# MOTOR_DRV.net
KiCad netlist of a schematic drawn in Altium Designer
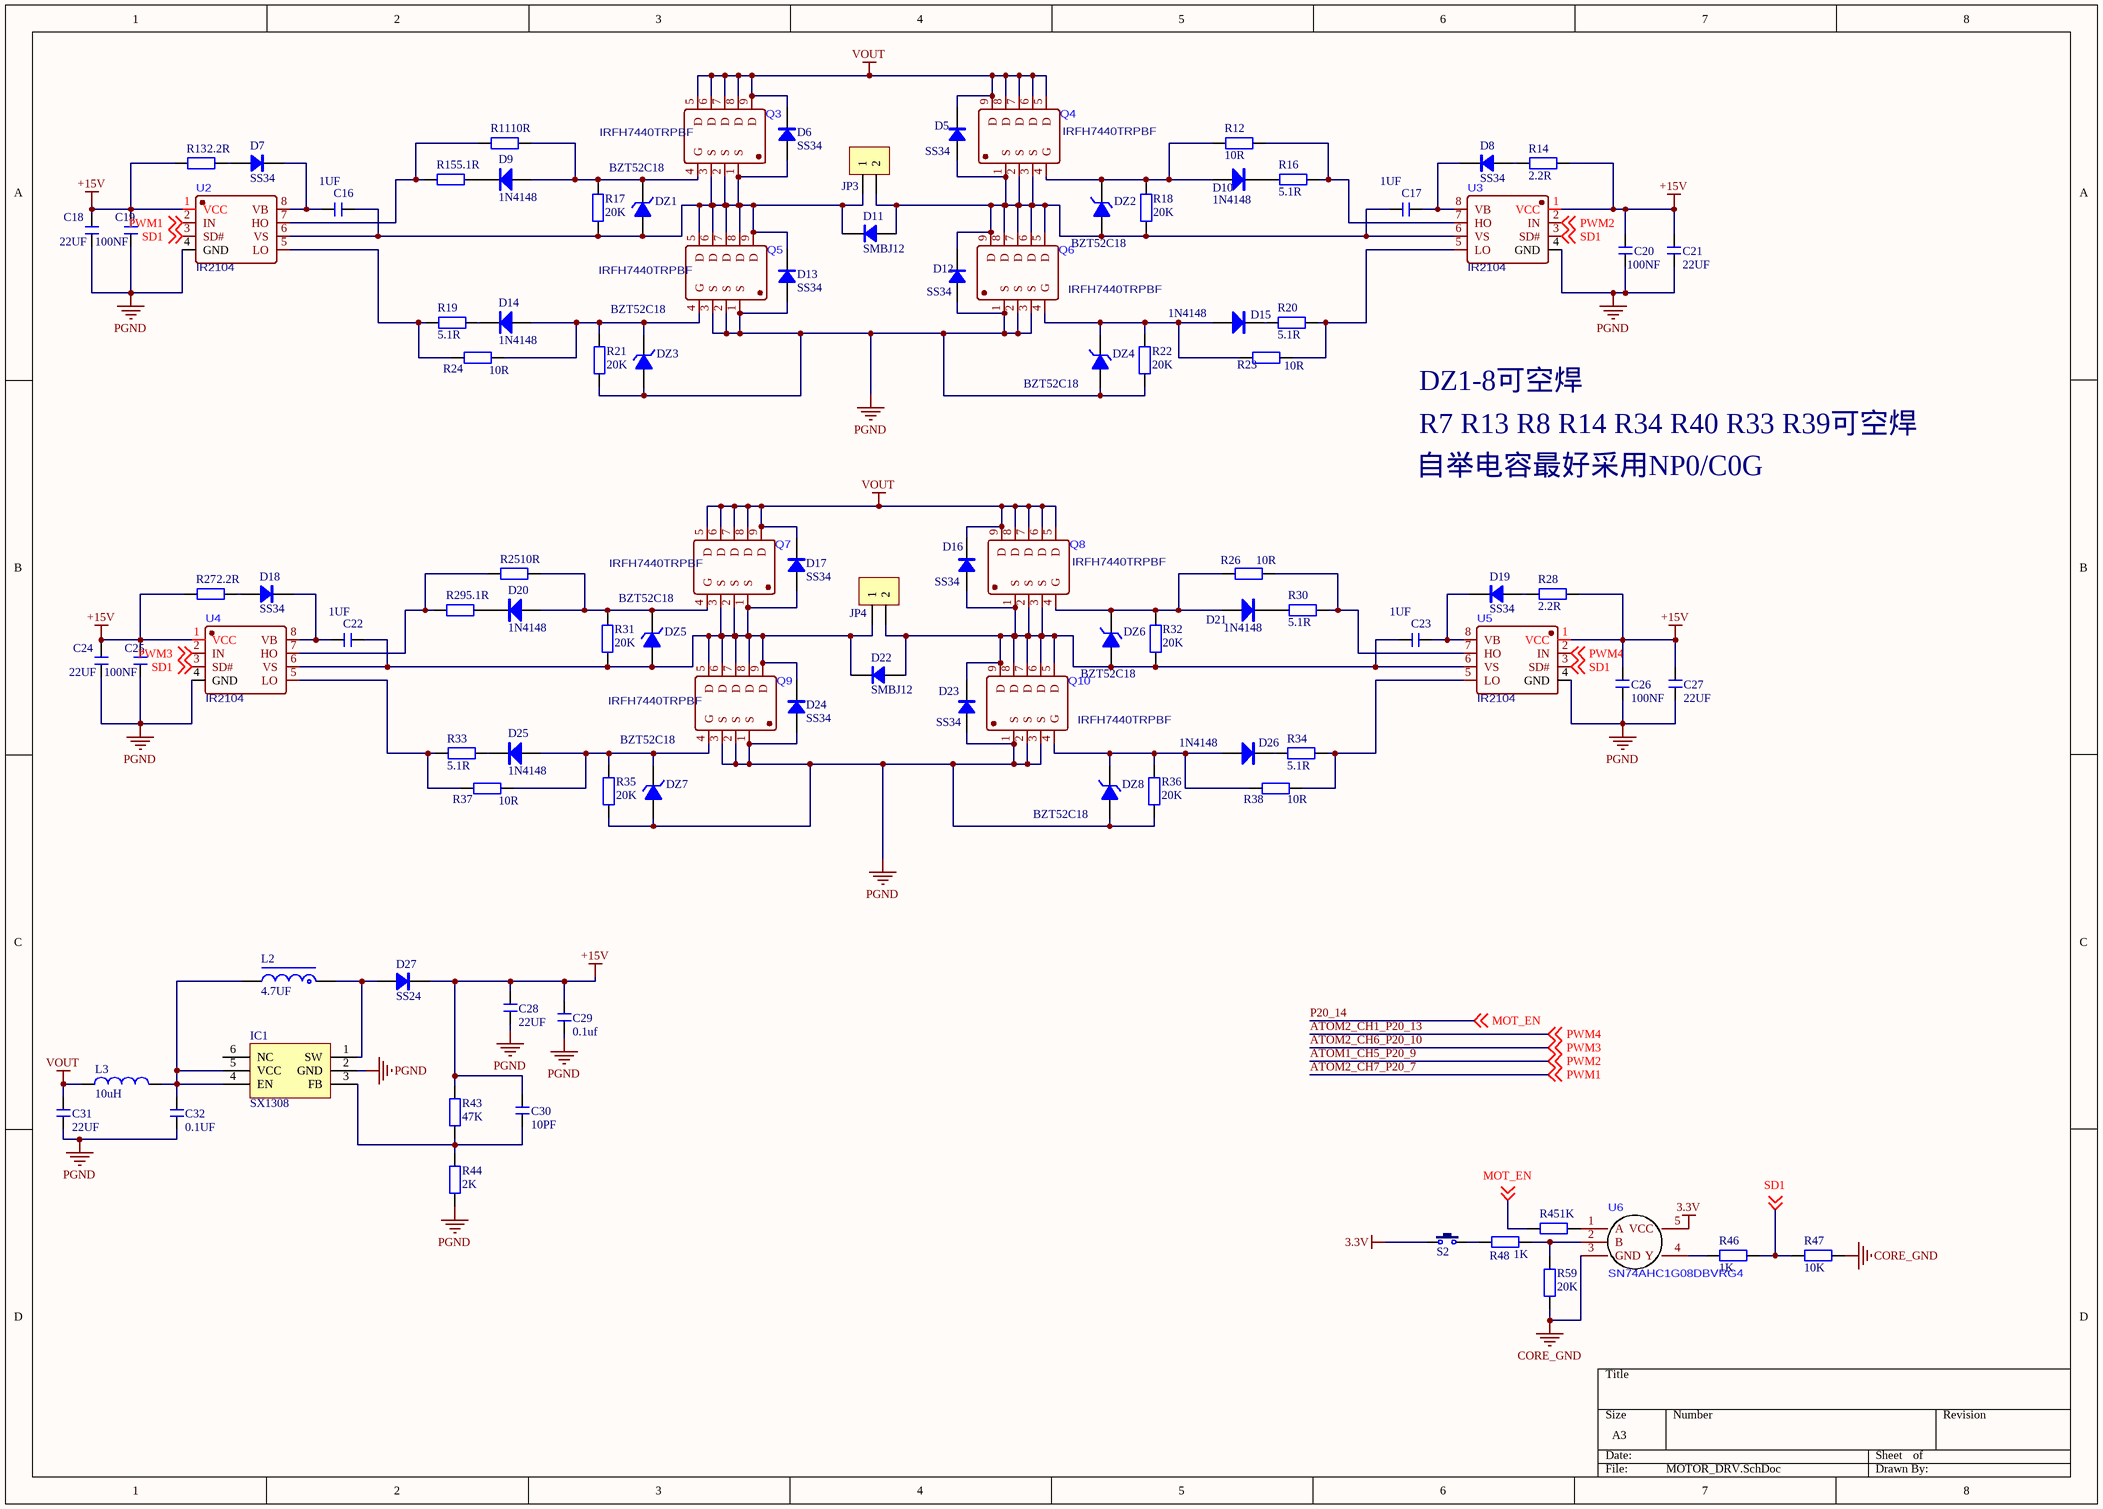
[diagram p0: MOTOR_DRV.SchDoc]

(export (version "E")
  (design (tool "Eeschema 10.0.6"))
  (components
    (comp (ref "C16")
      (value "1UF")
      (footprint "C 1206_L")
      (description "无极性贴片电容")
      (fields (field (name "版权归属") "源创客"))
      (libsource (lib "3.1   - 电阻-电容-电感") (part "C"))
    )
    (comp (ref "C17")
      (value "1UF")
      (footprint "C 1206_L")
      (description "无极性贴片电容")
      (fields (field (name "版权归属") "源创客"))
      (libsource (lib "3.1   - 电阻-电容-电感") (part "C"))
    )
    (comp (ref "C18")
      (value "22UF")
      (footprint "C 0805_L")
      (description "无极性贴片电容")
      (fields (field (name "版权归属") "源创客"))
      (libsource (lib "3.1   - 电阻-电容-电感") (part "C"))
    )
    (comp (ref "C19")
      (value "100NF")
      (footprint "C 0805_L")
      (description "无极性贴片电容")
      (fields (field (name "版权归属") "源创客"))
      (libsource (lib "3.1   - 电阻-电容-电感") (part "C"))
    )
    (comp (ref "C20")
      (value "100NF")
      (footprint "C 0805_L")
      (description "无极性贴片电容")
      (fields (field (name "版权归属") "源创客"))
      (libsource (lib "3.1   - 电阻-电容-电感") (part "C"))
    )
    (comp (ref "C21")
      (value "22UF")
      (footprint "C 0805_L")
      (description "无极性贴片电容")
      (fields (field (name "版权归属") "源创客"))
      (libsource (lib "3.1   - 电阻-电容-电感") (part "C"))
    )
    (comp (ref "C22")
      (value "1UF")
      (footprint "C 1206_L")
      (description "无极性贴片电容")
      (fields (field (name "版权归属") "源创客"))
      (libsource (lib "3.1   - 电阻-电容-电感") (part "C"))
    )
    (comp (ref "C23")
      (value "1UF")
      (footprint "C 1206_L")
      (description "无极性贴片电容")
      (fields (field (name "版权归属") "源创客"))
      (libsource (lib "3.1   - 电阻-电容-电感") (part "C"))
    )
    (comp (ref "C24")
      (value "22UF")
      (footprint "C 0805_L")
      (description "无极性贴片电容")
      (fields (field (name "版权归属") "源创客"))
      (libsource (lib "3.1   - 电阻-电容-电感") (part "C"))
    )
    (comp (ref "C25")
      (value "100NF")
      (footprint "C 0805_L")
      (description "无极性贴片电容")
      (fields (field (name "版权归属") "源创客"))
      (libsource (lib "3.1   - 电阻-电容-电感") (part "C"))
    )
    (comp (ref "C26")
      (value "100NF")
      (footprint "C 0805_L")
      (description "无极性贴片电容")
      (fields (field (name "版权归属") "源创客"))
      (libsource (lib "3.1   - 电阻-电容-电感") (part "C"))
    )
    (comp (ref "C27")
      (value "22UF")
      (footprint "C 0805_L")
      (description "无极性贴片电容")
      (fields (field (name "版权归属") "源创客"))
      (libsource (lib "3.1   - 电阻-电容-电感") (part "C"))
    )
    (comp (ref "C28")
      (value "22UF")
      (footprint "C 0805_L")
      (description "无极性贴片电容")
      (fields (field (name "版权归属") "源创客"))
      (libsource (lib "3.1   - 电阻-电容-电感") (part "C"))
    )
    (comp (ref "C29")
      (value "0.1uf")
      (footprint "C 0805_L")
      (description "无极性贴片电容")
      (fields (field (name "版权归属") "源创客"))
      (libsource (lib "3.1   - 电阻-电容-电感") (part "C"))
    )
    (comp (ref "C30")
      (value "10PF")
      (footprint "C 0805_L")
      (description "无极性贴片电容")
      (fields (field (name "版权归属") "源创客"))
      (libsource (lib "3.1   - 电阻-电容-电感") (part "C"))
    )
    (comp (ref "C31")
      (value "22UF")
      (footprint "C 0805_L")
      (description "无极性贴片电容")
      (fields (field (name "版权归属") "源创客"))
      (libsource (lib "3.1   - 电阻-电容-电感") (part "C"))
    )
    (comp (ref "C32")
      (value "0.1UF")
      (footprint "C 0805_L")
      (description "无极性贴片电容")
      (fields (field (name "版权归属") "源创客"))
      (libsource (lib "3.1   - 电阻-电容-电感") (part "C"))
    )
    (comp (ref "D5")
      (value "SS34")
      (footprint "SMA")
      (description "肖特基二极管")
      (fields (field (name "版权归属") "源创客"))
      (libsource (lib "8.1   - 二极管-整流桥") (part "SS34"))
    )
    (comp (ref "D6")
      (value "SS34")
      (footprint "SMA")
      (description "肖特基二极管")
      (fields (field (name "版权归属") "源创客"))
      (libsource (lib "8.1   - 二极管-整流桥") (part "SS34"))
    )
    (comp (ref "D7")
      (value "SS34")
      (footprint "SMA")
      (description "肖特基二极管")
      (fields (field (name "版权归属") "源创客"))
      (libsource (lib "8.1   - 二极管-整流桥") (part "SS34"))
    )
    (comp (ref "D8")
      (value "SS34")
      (footprint "SMA")
      (description "肖特基二极管")
      (fields (field (name "版权归属") "源创客"))
      (libsource (lib "8.1   - 二极管-整流桥") (part "SS34"))
    )
    (comp (ref "D9")
      (value "1N4148")
      (footprint "SOD-123")
      (description "高速开关二极管")
      (fields (field (name "版权归属") "源创客"))
      (libsource (lib "8.1   - 二极管-整流桥") (part "1N4148"))
    )
    (comp (ref "D10")
      (value "1N4148")
      (footprint "SOD-123")
      (description "高速开关二极管")
      (fields (field (name "版权归属") "源创客"))
      (libsource (lib "8.1   - 二极管-整流桥") (part "1N4148"))
    )
    (comp (ref "D11")
      (value "SMBJ12")
      (footprint "SMA")
      (description "肖特基二极管")
      (fields (field (name "版权归属") "源创客"))
      (libsource (lib "8.1   - 二极管-整流桥") (part "SS34"))
    )
    (comp (ref "D12")
      (value "SS34")
      (footprint "SMA")
      (description "肖特基二极管")
      (fields (field (name "版权归属") "源创客"))
      (libsource (lib "8.1   - 二极管-整流桥") (part "SS34"))
    )
    (comp (ref "D13")
      (value "SS34")
      (footprint "SMA")
      (description "肖特基二极管")
      (fields (field (name "版权归属") "源创客"))
      (libsource (lib "8.1   - 二极管-整流桥") (part "SS34"))
    )
    (comp (ref "D14")
      (value "1N4148")
      (footprint "SOD-123")
      (description "高速开关二极管")
      (fields (field (name "版权归属") "源创客"))
      (libsource (lib "8.1   - 二极管-整流桥") (part "1N4148"))
    )
    (comp (ref "D15")
      (value "1N4148")
      (footprint "SOD-123")
      (description "高速开关二极管")
      (fields (field (name "版权归属") "源创客"))
      (libsource (lib "8.1   - 二极管-整流桥") (part "1N4148"))
    )
    (comp (ref "D16")
      (value "SS34")
      (footprint "SMA")
      (description "肖特基二极管")
      (fields (field (name "版权归属") "源创客"))
      (libsource (lib "8.1   - 二极管-整流桥") (part "SS34"))
    )
    (comp (ref "D17")
      (value "SS34")
      (footprint "SMA")
      (description "肖特基二极管")
      (fields (field (name "版权归属") "源创客"))
      (libsource (lib "8.1   - 二极管-整流桥") (part "SS34"))
    )
    (comp (ref "D18")
      (value "SS34")
      (footprint "SMA")
      (description "肖特基二极管")
      (fields (field (name "版权归属") "源创客"))
      (libsource (lib "8.1   - 二极管-整流桥") (part "SS34"))
    )
    (comp (ref "D19")
      (value "SS34")
      (footprint "SMA")
      (description "肖特基二极管")
      (fields (field (name "版权归属") "源创客"))
      (libsource (lib "8.1   - 二极管-整流桥") (part "SS34"))
    )
    (comp (ref "D20")
      (value "1N4148")
      (footprint "SOD-123")
      (description "高速开关二极管")
      (fields (field (name "版权归属") "源创客"))
      (libsource (lib "8.1   - 二极管-整流桥") (part "1N4148"))
    )
    (comp (ref "D21")
      (value "1N4148")
      (footprint "SOD-123")
      (description "高速开关二极管")
      (fields (field (name "版权归属") "源创客"))
      (libsource (lib "8.1   - 二极管-整流桥") (part "1N4148"))
    )
    (comp (ref "D22")
      (value "SMBJ12")
      (footprint "SMA")
      (description "肖特基二极管")
      (fields (field (name "版权归属") "源创客"))
      (libsource (lib "8.1   - 二极管-整流桥") (part "SS34"))
    )
    (comp (ref "D23")
      (value "SS34")
      (footprint "SMA")
      (description "肖特基二极管")
      (fields (field (name "版权归属") "源创客"))
      (libsource (lib "8.1   - 二极管-整流桥") (part "SS34"))
    )
    (comp (ref "D24")
      (value "SS34")
      (footprint "SMA")
      (description "肖特基二极管")
      (fields (field (name "版权归属") "源创客"))
      (libsource (lib "8.1   - 二极管-整流桥") (part "SS34"))
    )
    (comp (ref "D25")
      (value "1N4148")
      (footprint "SOD-123")
      (description "高速开关二极管")
      (fields (field (name "版权归属") "源创客"))
      (libsource (lib "8.1   - 二极管-整流桥") (part "1N4148"))
    )
    (comp (ref "D26")
      (value "1N4148")
      (footprint "SOD-123")
      (description "高速开关二极管")
      (fields (field (name "版权归属") "源创客"))
      (libsource (lib "8.1   - 二极管-整流桥") (part "1N4148"))
    )
    (comp (ref "D27")
      (value "SS24")
      (footprint "SMA")
      (description "肖特基二极管")
      (fields (field (name "版权归属") "源创客"))
      (libsource (lib "8.1   - 二极管-整流桥") (part "SS24"))
    )
    (comp (ref "DZ1")
      (value "BZT52C18")
      (footprint "SOD-123")
      (description "18V稳压管")
      (fields (field (name "版权归属") "源创客"))
      (libsource (lib "8.1   - 二极管-整流桥") (part "1N4102"))
    )
    (comp (ref "DZ2")
      (value "BZT52C18")
      (footprint "SOD-123")
      (description "18V稳压管")
      (fields (field (name "版权归属") "源创客"))
      (libsource (lib "8.1   - 二极管-整流桥") (part "1N4102"))
    )
    (comp (ref "DZ3")
      (value "BZT52C18")
      (footprint "SOD-123")
      (description "18V稳压管")
      (fields (field (name "版权归属") "源创客"))
      (libsource (lib "8.1   - 二极管-整流桥") (part "1N4102"))
    )
    (comp (ref "DZ4")
      (value "BZT52C18")
      (footprint "SOD-123")
      (description "18V稳压管")
      (fields (field (name "版权归属") "源创客"))
      (libsource (lib "8.1   - 二极管-整流桥") (part "1N4102"))
    )
    (comp (ref "DZ5")
      (value "BZT52C18")
      (footprint "SOD-123")
      (description "18V稳压管")
      (fields (field (name "版权归属") "源创客"))
      (libsource (lib "8.1   - 二极管-整流桥") (part "1N4102"))
    )
    (comp (ref "DZ6")
      (value "BZT52C18")
      (footprint "SOD-123")
      (description "18V稳压管")
      (fields (field (name "版权归属") "源创客"))
      (libsource (lib "8.1   - 二极管-整流桥") (part "1N4102"))
    )
    (comp (ref "DZ7")
      (value "BZT52C18")
      (footprint "SOD-123")
      (description "18V稳压管")
      (fields (field (name "版权归属") "源创客"))
      (libsource (lib "8.1   - 二极管-整流桥") (part "1N4102"))
    )
    (comp (ref "DZ8")
      (value "BZT52C18")
      (footprint "SOD-123")
      (description "18V稳压管")
      (fields (field (name "版权归属") "源创客"))
      (libsource (lib "8.1   - 二极管-整流桥") (part "1N4102"))
    )
    (comp (ref "IC1")
      (value "SX1308")
      (footprint "SOT23-6N")
      (description "可调升压芯片")
      (fields (field (name "版权归属") "源创客"))
      (libsource (lib "1.3   - 电源类芯片") (part "SX1308"))
    )
    (comp (ref "JP3")
      (value "HDR-1X2")
      (footprint "KF2EDGK5.08-LI-2P")
      (description "2P接插件")
      (fields (field (name "版权归属") "源创客"))
      (libsource (lib "4.11 - 接插件-脚距5.08") (part "Header 2"))
    )
    (comp (ref "JP4")
      (value "HDR-1X2")
      (footprint "KF2EDGK5.08-LI-2P")
      (description "2P接插件")
      (fields (field (name "版权归属") "源创客"))
      (libsource (lib "4.11 - 接插件-脚距5.08") (part "Header 2"))
    )
    (comp (ref "L2")
      (value "4.7UF")
      (footprint "L-SMD-0630")
      (description "功率屏蔽电感")
      (fields (field (name "版权归属") "源创客"))
      (libsource (lib "3.1   - 电阻-电容-电感") (part "L-CDRH"))
    )
    (comp (ref "L3")
      (value "10uH")
      (footprint "L 0805_L")
      (description "小功率贴片电感")
      (fields (field (name "版权归属") "源创客"))
      (libsource (lib "3.1   - 电阻-电容-电感") (part "L"))
    )
    (comp (ref "Q3")
      (value "IRFH7440TRPBF")
      (footprint "PQFN-8P_L5.8-W4.9-P1.27-LS6.0-BL")
      (libsource (lib "IRFH7440TRPBF") (part "IRFH7440TRPBF"))
    )
    (comp (ref "Q4")
      (value "IRFH7440TRPBF")
      (footprint "PQFN-8P_L5.8-W4.9-P1.27-LS6.0-BL")
      (libsource (lib "IRFH7440TRPBF") (part "IRFH7440TRPBF"))
    )
    (comp (ref "Q5")
      (value "IRFH7440TRPBF")
      (footprint "PQFN-8P_L5.8-W4.9-P1.27-LS6.0-BL")
      (libsource (lib "IRFH7440TRPBF") (part "IRFH7440TRPBF"))
    )
    (comp (ref "Q6")
      (value "IRFH7440TRPBF")
      (footprint "PQFN-8P_L5.8-W4.9-P1.27-LS6.0-BL")
      (libsource (lib "IRFH7440TRPBF") (part "IRFH7440TRPBF"))
    )
    (comp (ref "Q7")
      (value "IRFH7440TRPBF")
      (footprint "PQFN-8P_L5.8-W4.9-P1.27-LS6.0-BL")
      (libsource (lib "IRFH7440TRPBF") (part "IRFH7440TRPBF"))
    )
    (comp (ref "Q8")
      (value "IRFH7440TRPBF")
      (footprint "PQFN-8P_L5.8-W4.9-P1.27-LS6.0-BL")
      (libsource (lib "IRFH7440TRPBF") (part "IRFH7440TRPBF"))
    )
    (comp (ref "Q9")
      (value "IRFH7440TRPBF")
      (footprint "PQFN-8P_L5.8-W4.9-P1.27-LS6.0-BL")
      (libsource (lib "IRFH7440TRPBF") (part "IRFH7440TRPBF"))
    )
    (comp (ref "Q10")
      (value "IRFH7440TRPBF")
      (footprint "PQFN-8P_L5.8-W4.9-P1.27-LS6.0-BL")
      (libsource (lib "IRFH7440TRPBF") (part "IRFH7440TRPBF"))
    )
    (comp (ref "R11")
      (value "10R")
      (footprint "R 0805_L")
      (description "贴片电阻")
      (fields (field (name "版权归属") "源创客"))
      (libsource (lib "3.1   - 电阻-电容-电感") (part "R"))
    )
    (comp (ref "R12")
      (value "10R")
      (footprint "R 0805_L")
      (description "贴片电阻")
      (fields (field (name "版权归属") "源创客"))
      (libsource (lib "3.1   - 电阻-电容-电感") (part "R"))
    )
    (comp (ref "R13")
      (value "2.2R")
      (footprint "R 0805_L")
      (description "贴片电阻")
      (fields (field (name "版权归属") "源创客"))
      (libsource (lib "3.1   - 电阻-电容-电感") (part "R"))
    )
    (comp (ref "R14")
      (value "2.2R")
      (footprint "R 0805_L")
      (description "贴片电阻")
      (fields (field (name "版权归属") "源创客"))
      (libsource (lib "3.1   - 电阻-电容-电感") (part "R"))
    )
    (comp (ref "R15")
      (value "5.1R")
      (footprint "R 0805_L")
      (description "贴片电阻")
      (fields (field (name "版权归属") "源创客"))
      (libsource (lib "3.1   - 电阻-电容-电感") (part "R"))
    )
    (comp (ref "R16")
      (value "5.1R")
      (footprint "R 0805_L")
      (description "贴片电阻")
      (fields (field (name "版权归属") "源创客"))
      (libsource (lib "3.1   - 电阻-电容-电感") (part "R"))
    )
    (comp (ref "R17")
      (value "20K")
      (footprint "R 0805_L")
      (description "贴片电阻")
      (fields (field (name "版权归属") "源创客"))
      (libsource (lib "3.1   - 电阻-电容-电感") (part "R"))
    )
    (comp (ref "R18")
      (value "20K")
      (footprint "R 0805_L")
      (description "贴片电阻")
      (fields (field (name "版权归属") "源创客"))
      (libsource (lib "3.1   - 电阻-电容-电感") (part "R"))
    )
    (comp (ref "R19")
      (value "5.1R")
      (footprint "R 0805_L")
      (description "贴片电阻")
      (fields (field (name "版权归属") "源创客"))
      (libsource (lib "3.1   - 电阻-电容-电感") (part "R"))
    )
    (comp (ref "R20")
      (value "5.1R")
      (footprint "R 0805_L")
      (description "贴片电阻")
      (fields (field (name "版权归属") "源创客"))
      (libsource (lib "3.1   - 电阻-电容-电感") (part "R"))
    )
    (comp (ref "R21")
      (value "20K")
      (footprint "R 0805_L")
      (description "贴片电阻")
      (fields (field (name "版权归属") "源创客"))
      (libsource (lib "3.1   - 电阻-电容-电感") (part "R"))
    )
    (comp (ref "R22")
      (value "20K")
      (footprint "R 0805_L")
      (description "贴片电阻")
      (fields (field (name "版权归属") "源创客"))
      (libsource (lib "3.1   - 电阻-电容-电感") (part "R"))
    )
    (comp (ref "R23")
      (value "10R")
      (footprint "R 0805_L")
      (description "贴片电阻")
      (fields (field (name "版权归属") "源创客"))
      (libsource (lib "3.1   - 电阻-电容-电感") (part "R"))
    )
    (comp (ref "R24")
      (value "10R")
      (footprint "R 0805_L")
      (description "贴片电阻")
      (fields (field (name "版权归属") "源创客"))
      (libsource (lib "3.1   - 电阻-电容-电感") (part "R"))
    )
    (comp (ref "R25")
      (value "10R")
      (footprint "R 0805_L")
      (description "贴片电阻")
      (fields (field (name "版权归属") "源创客"))
      (libsource (lib "3.1   - 电阻-电容-电感") (part "R"))
    )
    (comp (ref "R26")
      (value "10R")
      (footprint "R 0805_L")
      (description "贴片电阻")
      (fields (field (name "版权归属") "源创客"))
      (libsource (lib "3.1   - 电阻-电容-电感") (part "R"))
    )
    (comp (ref "R27")
      (value "2.2R")
      (footprint "R 0805_L")
      (description "贴片电阻")
      (fields (field (name "版权归属") "源创客"))
      (libsource (lib "3.1   - 电阻-电容-电感") (part "R"))
    )
    (comp (ref "R28")
      (value "2.2R")
      (footprint "R 0805_L")
      (description "贴片电阻")
      (fields (field (name "版权归属") "源创客"))
      (libsource (lib "3.1   - 电阻-电容-电感") (part "R"))
    )
    (comp (ref "R29")
      (value "5.1R")
      (footprint "R 0805_L")
      (description "贴片电阻")
      (fields (field (name "版权归属") "源创客"))
      (libsource (lib "3.1   - 电阻-电容-电感") (part "R"))
    )
    (comp (ref "R30")
      (value "5.1R")
      (footprint "R 0805_L")
      (description "贴片电阻")
      (fields (field (name "版权归属") "源创客"))
      (libsource (lib "3.1   - 电阻-电容-电感") (part "R"))
    )
    (comp (ref "R31")
      (value "20K")
      (footprint "R 0805_L")
      (description "贴片电阻")
      (fields (field (name "版权归属") "源创客"))
      (libsource (lib "3.1   - 电阻-电容-电感") (part "R"))
    )
    (comp (ref "R32")
      (value "20K")
      (footprint "R 0805_L")
      (description "贴片电阻")
      (fields (field (name "版权归属") "源创客"))
      (libsource (lib "3.1   - 电阻-电容-电感") (part "R"))
    )
    (comp (ref "R33")
      (value "5.1R")
      (footprint "R 0805_L")
      (description "贴片电阻")
      (fields (field (name "版权归属") "源创客"))
      (libsource (lib "3.1   - 电阻-电容-电感") (part "R"))
    )
    (comp (ref "R34")
      (value "5.1R")
      (footprint "R 0805_L")
      (description "贴片电阻")
      (fields (field (name "版权归属") "源创客"))
      (libsource (lib "3.1   - 电阻-电容-电感") (part "R"))
    )
    (comp (ref "R35")
      (value "20K")
      (footprint "R 0805_L")
      (description "贴片电阻")
      (fields (field (name "版权归属") "源创客"))
      (libsource (lib "3.1   - 电阻-电容-电感") (part "R"))
    )
    (comp (ref "R36")
      (value "20K")
      (footprint "R 0805_L")
      (description "贴片电阻")
      (fields (field (name "版权归属") "源创客"))
      (libsource (lib "3.1   - 电阻-电容-电感") (part "R"))
    )
    (comp (ref "R37")
      (value "10R")
      (footprint "R 0805_L")
      (description "贴片电阻")
      (fields (field (name "版权归属") "源创客"))
      (libsource (lib "3.1   - 电阻-电容-电感") (part "R"))
    )
    (comp (ref "R38")
      (value "10R")
      (footprint "R 0805_L")
      (description "贴片电阻")
      (fields (field (name "版权归属") "源创客"))
      (libsource (lib "3.1   - 电阻-电容-电感") (part "R"))
    )
    (comp (ref "R43")
      (value "47K")
      (footprint "R 0805_L")
      (description "贴片电阻")
      (fields (field (name "版权归属") "源创客"))
      (libsource (lib "3.1   - 电阻-电容-电感") (part "R"))
    )
    (comp (ref "R44")
      (value "2K")
      (footprint "R 0805_L")
      (description "贴片电阻")
      (fields (field (name "版权归属") "源创客"))
      (libsource (lib "3.1   - 电阻-电容-电感") (part "R"))
    )
    (comp (ref "R45")
      (value "1K")
      (footprint "R 0805_L")
      (description "贴片电阻")
      (fields (field (name "版权归属") "源创客"))
      (libsource (lib "3.1   - 电阻-电容-电感") (part "R"))
    )
    (comp (ref "R46")
      (value "1K")
      (footprint "R 0805_L")
      (description "贴片电阻")
      (fields (field (name "版权归属") "源创客"))
      (libsource (lib "3.1   - 电阻-电容-电感") (part "R"))
    )
    (comp (ref "R47")
      (value "10K")
      (footprint "R 0805_L")
      (description "贴片电阻")
      (fields (field (name "版权归属") "源创客"))
      (libsource (lib "3.1   - 电阻-电容-电感") (part "R"))
    )
    (comp (ref "R48")
      (value "1K")
      (footprint "R 0805_L")
      (description "贴片电阻")
      (fields (field (name "版权归属") "源创客"))
      (libsource (lib "3.1   - 电阻-电容-电感") (part "R"))
    )
    (comp (ref "R59")
      (value "20K")
      (footprint "R 0805_L")
      (description "贴片电阻")
      (fields (field (name "版权归属") "源创客"))
      (libsource (lib "3.1   - 电阻-电容-电感") (part "R"))
    )
    (comp (ref "S2")
      (value "6x6x5")
      (footprint "KEY-TH_CN-KCD11")
      (description "2脚直插6x6轻触开关")
      (fields (field (name "版权归属") "源创客"))
      (libsource (lib "5.1   - 按键-开关") (part "TSW DIP-2Pin-6x6"))
    )
    (comp (ref "U2") (value "IR2104") (footprint "SOP8_M") (libsource (lib "EG2104") (part "EG2104")))
    (comp (ref "U3") (value "IR2104") (footprint "SOP8_M") (libsource (lib "EG2104") (part "EG2104")))
    (comp (ref "U4") (value "IR2104") (footprint "SOP8_M") (libsource (lib "EG2104") (part "EG2104")))
    (comp (ref "U5") (value "IR2104") (footprint "SOP8_M") (libsource (lib "EG2104") (part "EG2104")))
    (comp (ref "U6")
      (value "SN74AHC1G08DBVRG4")
      (footprint "SOT23-5L")
      (libsource (lib "SN74AHC1G08DBVRG4") (part "SN74AHC1G08DBVRG4"))
    )
  )
  (nets
    (net (code "1") (name "+15V") (class "Default")
      (node (ref "C18") (pin "2") (pinfunction "2_2") (pintype "passive"))
      (node (ref "C19") (pin "2") (pinfunction "2_2") (pintype "passive"))
      (node (ref "C20") (pin "2") (pinfunction "2_2") (pintype "passive"))
      (node (ref "C21") (pin "2") (pinfunction "2_2") (pintype "passive"))
      (node (ref "C24") (pin "2") (pinfunction "2_2") (pintype "passive"))
      (node (ref "C25") (pin "2") (pinfunction "2_2") (pintype "passive"))
      (node (ref "C26") (pin "2") (pinfunction "2_2") (pintype "passive"))
      (node (ref "C27") (pin "2") (pinfunction "2_2") (pintype "passive"))
      (node (ref "C28") (pin "1") (pinfunction "1_1") (pintype "passive"))
      (node (ref "C29") (pin "1") (pinfunction "1_1") (pintype "passive"))
      (node (ref "C30") (pin "1") (pinfunction "1_1") (pintype "passive"))
      (node (ref "D27") (pin "2") (pinfunction "K_2") (pintype "passive"))
      (node (ref "R13") (pin "1") (pinfunction "1_1") (pintype "passive"))
      (node (ref "R14") (pin "1") (pinfunction "1_1") (pintype "passive"))
      (node (ref "R27") (pin "1") (pinfunction "1_1") (pintype "passive"))
      (node (ref "R28") (pin "1") (pinfunction "1_1") (pintype "passive"))
      (node (ref "R43") (pin "1") (pinfunction "1_1") (pintype "passive"))
      (node (ref "U2") (pin "1") (pinfunction "VCC_1") (pintype "passive"))
      (node (ref "U3") (pin "1") (pinfunction "VCC_1") (pintype "passive"))
      (node (ref "U4") (pin "1") (pinfunction "VCC_1") (pintype "passive"))
      (node (ref "U5") (pin "1") (pinfunction "VCC_1") (pintype "passive"))
    )
    (net (code "2") (name "3.3V") (class "Default")
      (node (ref "S2") (pin "1") (pinfunction "1_1") (pintype "passive"))
      (node (ref "U6") (pin "5") (pinfunction "VCC_5") (pintype "passive"))
    )
    (net (code "3") (name "CORE_GND") (class "Default")
      (node (ref "R47") (pin "2") (pinfunction "2_2") (pintype "passive"))
      (node (ref "R59") (pin "2") (pinfunction "2_2") (pintype "passive"))
      (node (ref "U6") (pin "3") (pinfunction "GND_3") (pintype "passive"))
    )
    (net (code "4") (name "MOT_EN") (class "Default")
      (node (ref "R45") (pin "2") (pinfunction "2_2") (pintype "passive"))
    )
    (net (code "5") (name "Net-(D7-A)") (class "Default")
      (node (ref "D7") (pin "1") (pinfunction "A_1") (pintype "passive"))
      (node (ref "R13") (pin "2") (pinfunction "2_2") (pintype "passive"))
    )
    (net (code "6") (name "Net-(D7-K)") (class "Default")
      (node (ref "C16") (pin "2") (pinfunction "2_2") (pintype "passive"))
      (node (ref "D7") (pin "2") (pinfunction "K_2") (pintype "passive"))
      (node (ref "U2") (pin "8") (pinfunction "VB_8") (pintype "passive"))
    )
    (net (code "7") (name "Net-(D8-A)") (class "Default")
      (node (ref "D8") (pin "1") (pinfunction "A_1") (pintype "passive"))
      (node (ref "R14") (pin "2") (pinfunction "2_2") (pintype "passive"))
    )
    (net (code "8") (name "Net-(D8-K)") (class "Default")
      (node (ref "C17") (pin "2") (pinfunction "2_2") (pintype "passive"))
      (node (ref "D8") (pin "2") (pinfunction "K_2") (pintype "passive"))
      (node (ref "U3") (pin "8") (pinfunction "VB_8") (pintype "passive"))
    )
    (net (code "9") (name "Net-(D9-A)") (class "Default")
      (node (ref "D9") (pin "1") (pinfunction "A_1") (pintype "passive"))
      (node (ref "DZ1") (pin "2") (pinfunction "K_2") (pintype "passive"))
      (node (ref "Q3") (pin "4") (pinfunction "G_4") (pintype "passive"))
      (node (ref "R11") (pin "2") (pinfunction "2_2") (pintype "passive"))
      (node (ref "R17") (pin "2") (pinfunction "2_2") (pintype "passive"))
    )
    (net (code "10") (name "Net-(D9-K)") (class "Default")
      (node (ref "D9") (pin "2") (pinfunction "K_2") (pintype "passive"))
      (node (ref "R15") (pin "2") (pinfunction "2_2") (pintype "passive"))
    )
    (net (code "11") (name "Net-(D10-A)") (class "Default")
      (node (ref "D10") (pin "1") (pinfunction "A_1") (pintype "passive"))
      (node (ref "DZ2") (pin "2") (pinfunction "K_2") (pintype "passive"))
      (node (ref "Q4") (pin "4") (pinfunction "G_4") (pintype "passive"))
      (node (ref "R12") (pin "2") (pinfunction "2_2") (pintype "passive"))
      (node (ref "R18") (pin "2") (pinfunction "2_2") (pintype "passive"))
    )
    (net (code "12") (name "Net-(D10-K)") (class "Default")
      (node (ref "D10") (pin "2") (pinfunction "K_2") (pintype "passive"))
      (node (ref "R16") (pin "2") (pinfunction "2_2") (pintype "passive"))
    )
    (net (code "13") (name "Net-(D11-A)") (class "Default")
      (node (ref "C17") (pin "1") (pinfunction "1_1") (pintype "passive"))
      (node (ref "D11") (pin "1") (pinfunction "A_1") (pintype "passive"))
      (node (ref "D12") (pin "2") (pinfunction "K_2") (pintype "passive"))
      (node (ref "D5") (pin "1") (pinfunction "A_1") (pintype "passive"))
      (node (ref "DZ2") (pin "1") (pinfunction "A_1") (pintype "passive"))
      (node (ref "JP3") (pin "2") (pinfunction "2_2") (pintype "passive"))
      (node (ref "Q4") (pin "1") (pinfunction "S_1") (pintype "passive"))
      (node (ref "Q4") (pin "2") (pinfunction "S_2") (pintype "passive"))
      (node (ref "Q4") (pin "3") (pinfunction "S_3") (pintype "passive"))
      (node (ref "Q6") (pin "5") (pinfunction "D_5") (pintype "passive"))
      (node (ref "Q6") (pin "6") (pinfunction "D_6") (pintype "passive"))
      (node (ref "Q6") (pin "7") (pinfunction "D_7") (pintype "passive"))
      (node (ref "Q6") (pin "8") (pinfunction "D_8") (pintype "passive"))
      (node (ref "Q6") (pin "9") (pinfunction "D_9") (pintype "passive"))
      (node (ref "R18") (pin "1") (pinfunction "1_1") (pintype "passive"))
      (node (ref "U3") (pin "6") (pinfunction "VS_6") (pintype "passive"))
    )
    (net (code "14") (name "Net-(D11-K)") (class "Default")
      (node (ref "C16") (pin "1") (pinfunction "1_1") (pintype "passive"))
      (node (ref "D11") (pin "2") (pinfunction "K_2") (pintype "passive"))
      (node (ref "D13") (pin "2") (pinfunction "K_2") (pintype "passive"))
      (node (ref "D6") (pin "1") (pinfunction "A_1") (pintype "passive"))
      (node (ref "DZ1") (pin "1") (pinfunction "A_1") (pintype "passive"))
      (node (ref "JP3") (pin "1") (pinfunction "1_1") (pintype "passive"))
      (node (ref "Q3") (pin "1") (pinfunction "S_1") (pintype "passive"))
      (node (ref "Q3") (pin "2") (pinfunction "S_2") (pintype "passive"))
      (node (ref "Q3") (pin "3") (pinfunction "S_3") (pintype "passive"))
      (node (ref "Q5") (pin "5") (pinfunction "D_5") (pintype "passive"))
      (node (ref "Q5") (pin "6") (pinfunction "D_6") (pintype "passive"))
      (node (ref "Q5") (pin "7") (pinfunction "D_7") (pintype "passive"))
      (node (ref "Q5") (pin "8") (pinfunction "D_8") (pintype "passive"))
      (node (ref "Q5") (pin "9") (pinfunction "D_9") (pintype "passive"))
      (node (ref "R17") (pin "1") (pinfunction "1_1") (pintype "passive"))
      (node (ref "U2") (pin "6") (pinfunction "VS_6") (pintype "passive"))
    )
    (net (code "15") (name "Net-(D14-A)") (class "Default")
      (node (ref "D14") (pin "1") (pinfunction "A_1") (pintype "passive"))
      (node (ref "DZ3") (pin "2") (pinfunction "K_2") (pintype "passive"))
      (node (ref "Q5") (pin "4") (pinfunction "G_4") (pintype "passive"))
      (node (ref "R21") (pin "2") (pinfunction "2_2") (pintype "passive"))
      (node (ref "R24") (pin "2") (pinfunction "2_2") (pintype "passive"))
    )
    (net (code "16") (name "Net-(D14-K)") (class "Default")
      (node (ref "D14") (pin "2") (pinfunction "K_2") (pintype "passive"))
      (node (ref "R19") (pin "2") (pinfunction "2_2") (pintype "passive"))
    )
    (net (code "17") (name "Net-(D15-A)") (class "Default")
      (node (ref "D15") (pin "1") (pinfunction "A_1") (pintype "passive"))
      (node (ref "DZ4") (pin "2") (pinfunction "K_2") (pintype "passive"))
      (node (ref "Q6") (pin "4") (pinfunction "G_4") (pintype "passive"))
      (node (ref "R22") (pin "2") (pinfunction "2_2") (pintype "passive"))
      (node (ref "R23") (pin "2") (pinfunction "2_2") (pintype "passive"))
    )
    (net (code "18") (name "Net-(D15-K)") (class "Default")
      (node (ref "D15") (pin "2") (pinfunction "K_2") (pintype "passive"))
      (node (ref "R20") (pin "2") (pinfunction "2_2") (pintype "passive"))
    )
    (net (code "19") (name "Net-(D16-A)") (class "Default")
      (node (ref "C23") (pin "1") (pinfunction "1_1") (pintype "passive"))
      (node (ref "D16") (pin "1") (pinfunction "A_1") (pintype "passive"))
      (node (ref "D22") (pin "1") (pinfunction "A_1") (pintype "passive"))
      (node (ref "D23") (pin "2") (pinfunction "K_2") (pintype "passive"))
      (node (ref "DZ6") (pin "1") (pinfunction "A_1") (pintype "passive"))
      (node (ref "JP4") (pin "2") (pinfunction "2_2") (pintype "passive"))
      (node (ref "Q10") (pin "5") (pinfunction "D_5") (pintype "passive"))
      (node (ref "Q10") (pin "6") (pinfunction "D_6") (pintype "passive"))
      (node (ref "Q10") (pin "7") (pinfunction "D_7") (pintype "passive"))
      (node (ref "Q10") (pin "8") (pinfunction "D_8") (pintype "passive"))
      (node (ref "Q10") (pin "9") (pinfunction "D_9") (pintype "passive"))
      (node (ref "Q8") (pin "1") (pinfunction "S_1") (pintype "passive"))
      (node (ref "Q8") (pin "2") (pinfunction "S_2") (pintype "passive"))
      (node (ref "Q8") (pin "3") (pinfunction "S_3") (pintype "passive"))
      (node (ref "R32") (pin "1") (pinfunction "1_1") (pintype "passive"))
      (node (ref "U5") (pin "6") (pinfunction "VS_6") (pintype "passive"))
    )
    (net (code "20") (name "Net-(D17-A)") (class "Default")
      (node (ref "C22") (pin "1") (pinfunction "1_1") (pintype "passive"))
      (node (ref "D17") (pin "1") (pinfunction "A_1") (pintype "passive"))
      (node (ref "D22") (pin "2") (pinfunction "K_2") (pintype "passive"))
      (node (ref "D24") (pin "2") (pinfunction "K_2") (pintype "passive"))
      (node (ref "DZ5") (pin "1") (pinfunction "A_1") (pintype "passive"))
      (node (ref "JP4") (pin "1") (pinfunction "1_1") (pintype "passive"))
      (node (ref "Q7") (pin "1") (pinfunction "S_1") (pintype "passive"))
      (node (ref "Q7") (pin "2") (pinfunction "S_2") (pintype "passive"))
      (node (ref "Q7") (pin "3") (pinfunction "S_3") (pintype "passive"))
      (node (ref "Q9") (pin "5") (pinfunction "D_5") (pintype "passive"))
      (node (ref "Q9") (pin "6") (pinfunction "D_6") (pintype "passive"))
      (node (ref "Q9") (pin "7") (pinfunction "D_7") (pintype "passive"))
      (node (ref "Q9") (pin "8") (pinfunction "D_8") (pintype "passive"))
      (node (ref "Q9") (pin "9") (pinfunction "D_9") (pintype "passive"))
      (node (ref "R31") (pin "1") (pinfunction "1_1") (pintype "passive"))
      (node (ref "U4") (pin "6") (pinfunction "VS_6") (pintype "passive"))
    )
    (net (code "21") (name "Net-(D18-A)") (class "Default")
      (node (ref "D18") (pin "1") (pinfunction "A_1") (pintype "passive"))
      (node (ref "R27") (pin "2") (pinfunction "2_2") (pintype "passive"))
    )
    (net (code "22") (name "Net-(D18-K)") (class "Default")
      (node (ref "C22") (pin "2") (pinfunction "2_2") (pintype "passive"))
      (node (ref "D18") (pin "2") (pinfunction "K_2") (pintype "passive"))
      (node (ref "U4") (pin "8") (pinfunction "VB_8") (pintype "passive"))
    )
    (net (code "23") (name "Net-(D19-A)") (class "Default")
      (node (ref "D19") (pin "1") (pinfunction "A_1") (pintype "passive"))
      (node (ref "R28") (pin "2") (pinfunction "2_2") (pintype "passive"))
    )
    (net (code "24") (name "Net-(D19-K)") (class "Default")
      (node (ref "C23") (pin "2") (pinfunction "2_2") (pintype "passive"))
      (node (ref "D19") (pin "2") (pinfunction "K_2") (pintype "passive"))
      (node (ref "U5") (pin "8") (pinfunction "VB_8") (pintype "passive"))
    )
    (net (code "25") (name "Net-(D20-A)") (class "Default")
      (node (ref "D20") (pin "1") (pinfunction "A_1") (pintype "passive"))
      (node (ref "DZ5") (pin "2") (pinfunction "K_2") (pintype "passive"))
      (node (ref "Q7") (pin "4") (pinfunction "G_4") (pintype "passive"))
      (node (ref "R25") (pin "2") (pinfunction "2_2") (pintype "passive"))
      (node (ref "R31") (pin "2") (pinfunction "2_2") (pintype "passive"))
    )
    (net (code "26") (name "Net-(D20-K)") (class "Default")
      (node (ref "D20") (pin "2") (pinfunction "K_2") (pintype "passive"))
      (node (ref "R29") (pin "2") (pinfunction "2_2") (pintype "passive"))
    )
    (net (code "27") (name "Net-(D21-A)") (class "Default")
      (node (ref "D21") (pin "1") (pinfunction "A_1") (pintype "passive"))
      (node (ref "DZ6") (pin "2") (pinfunction "K_2") (pintype "passive"))
      (node (ref "Q8") (pin "4") (pinfunction "G_4") (pintype "passive"))
      (node (ref "R26") (pin "2") (pinfunction "2_2") (pintype "passive"))
      (node (ref "R32") (pin "2") (pinfunction "2_2") (pintype "passive"))
    )
    (net (code "28") (name "Net-(D21-K)") (class "Default")
      (node (ref "D21") (pin "2") (pinfunction "K_2") (pintype "passive"))
      (node (ref "R30") (pin "2") (pinfunction "2_2") (pintype "passive"))
    )
    (net (code "29") (name "Net-(D25-A)") (class "Default")
      (node (ref "D25") (pin "1") (pinfunction "A_1") (pintype "passive"))
      (node (ref "DZ7") (pin "2") (pinfunction "K_2") (pintype "passive"))
      (node (ref "Q9") (pin "4") (pinfunction "G_4") (pintype "passive"))
      (node (ref "R35") (pin "2") (pinfunction "2_2") (pintype "passive"))
      (node (ref "R37") (pin "2") (pinfunction "2_2") (pintype "passive"))
    )
    (net (code "30") (name "Net-(D25-K)") (class "Default")
      (node (ref "D25") (pin "2") (pinfunction "K_2") (pintype "passive"))
      (node (ref "R33") (pin "2") (pinfunction "2_2") (pintype "passive"))
    )
    (net (code "31") (name "Net-(D26-A)") (class "Default")
      (node (ref "D26") (pin "1") (pinfunction "A_1") (pintype "passive"))
      (node (ref "DZ8") (pin "2") (pinfunction "K_2") (pintype "passive"))
      (node (ref "Q10") (pin "4") (pinfunction "G_4") (pintype "passive"))
      (node (ref "R36") (pin "2") (pinfunction "2_2") (pintype "passive"))
      (node (ref "R38") (pin "2") (pinfunction "2_2") (pintype "passive"))
    )
    (net (code "32") (name "Net-(D26-K)") (class "Default")
      (node (ref "D26") (pin "2") (pinfunction "K_2") (pintype "passive"))
      (node (ref "R34") (pin "2") (pinfunction "2_2") (pintype "passive"))
    )
    (net (code "33") (name "Net-(D27-A)") (class "Default")
      (node (ref "D27") (pin "1") (pinfunction "A_1") (pintype "passive"))
      (node (ref "IC1") (pin "1") (pinfunction "SW_1") (pintype "passive"))
      (node (ref "L2") (pin "1") (pinfunction "1_1") (pintype "passive"))
    )
    (net (code "34") (name "Net-(IC1-EN)") (class "Default")
      (node (ref "C32") (pin "1") (pinfunction "1_1") (pintype "passive"))
      (node (ref "IC1") (pin "4") (pinfunction "EN_4") (pintype "passive"))
      (node (ref "IC1") (pin "5") (pinfunction "VCC_5") (pintype "passive"))
      (node (ref "L2") (pin "2") (pinfunction "2_2") (pintype "passive"))
      (node (ref "L3") (pin "2") (pinfunction "2_2") (pintype "passive"))
    )
    (net (code "35") (name "Net-(IC1-FB)") (class "Default")
      (node (ref "C30") (pin "2") (pinfunction "2_2") (pintype "passive"))
      (node (ref "IC1") (pin "3") (pinfunction "FB_3") (pintype "passive"))
      (node (ref "R43") (pin "2") (pinfunction "2_2") (pintype "passive"))
      (node (ref "R44") (pin "1") (pinfunction "1_1") (pintype "passive"))
    )
    (net (code "36") (name "Net-(R48-Pad2)") (class "Default")
      (node (ref "R48") (pin "2") (pinfunction "2_2") (pintype "passive"))
      (node (ref "S2") (pin "2") (pinfunction "2_2") (pintype "passive"))
    )
    (net (code "37") (name "Net-(U2-HO)") (class "Default")
      (node (ref "R11") (pin "1") (pinfunction "1_1") (pintype "passive"))
      (node (ref "R15") (pin "1") (pinfunction "1_1") (pintype "passive"))
      (node (ref "U2") (pin "7") (pinfunction "HO_7") (pintype "passive"))
    )
    (net (code "38") (name "Net-(U2-LO)") (class "Default")
      (node (ref "R19") (pin "1") (pinfunction "1_1") (pintype "passive"))
      (node (ref "R24") (pin "1") (pinfunction "1_1") (pintype "passive"))
      (node (ref "U2") (pin "5") (pinfunction "LO_5") (pintype "passive"))
    )
    (net (code "39") (name "Net-(U3-HO)") (class "Default")
      (node (ref "R12") (pin "1") (pinfunction "1_1") (pintype "passive"))
      (node (ref "R16") (pin "1") (pinfunction "1_1") (pintype "passive"))
      (node (ref "U3") (pin "7") (pinfunction "HO_7") (pintype "passive"))
    )
    (net (code "40") (name "Net-(U3-LO)") (class "Default")
      (node (ref "R20") (pin "1") (pinfunction "1_1") (pintype "passive"))
      (node (ref "R23") (pin "1") (pinfunction "1_1") (pintype "passive"))
      (node (ref "U3") (pin "5") (pinfunction "LO_5") (pintype "passive"))
    )
    (net (code "41") (name "Net-(U4-HO)") (class "Default")
      (node (ref "R25") (pin "1") (pinfunction "1_1") (pintype "passive"))
      (node (ref "R29") (pin "1") (pinfunction "1_1") (pintype "passive"))
      (node (ref "U4") (pin "7") (pinfunction "HO_7") (pintype "passive"))
    )
    (net (code "42") (name "Net-(U4-LO)") (class "Default")
      (node (ref "R33") (pin "1") (pinfunction "1_1") (pintype "passive"))
      (node (ref "R37") (pin "1") (pinfunction "1_1") (pintype "passive"))
      (node (ref "U4") (pin "5") (pinfunction "LO_5") (pintype "passive"))
    )
    (net (code "43") (name "Net-(U5-HO)") (class "Default")
      (node (ref "R26") (pin "1") (pinfunction "1_1") (pintype "passive"))
      (node (ref "R30") (pin "1") (pinfunction "1_1") (pintype "passive"))
      (node (ref "U5") (pin "7") (pinfunction "HO_7") (pintype "passive"))
    )
    (net (code "44") (name "Net-(U5-LO)") (class "Default")
      (node (ref "R34") (pin "1") (pinfunction "1_1") (pintype "passive"))
      (node (ref "R38") (pin "1") (pinfunction "1_1") (pintype "passive"))
      (node (ref "U5") (pin "5") (pinfunction "LO_5") (pintype "passive"))
    )
    (net (code "45") (name "Net-(U6-A)") (class "Default")
      (node (ref "R45") (pin "1") (pinfunction "1_1") (pintype "passive"))
      (node (ref "U6") (pin "1") (pinfunction "A_1") (pintype "passive"))
    )
    (net (code "46") (name "Net-(U6-B)") (class "Default")
      (node (ref "R48") (pin "1") (pinfunction "1_1") (pintype "passive"))
      (node (ref "R59") (pin "1") (pinfunction "1_1") (pintype "passive"))
      (node (ref "U6") (pin "2") (pinfunction "B_2") (pintype "passive"))
    )
    (net (code "47") (name "Net-(U6-Y)") (class "Default")
      (node (ref "R46") (pin "1") (pinfunction "1_1") (pintype "passive"))
      (node (ref "U6") (pin "4") (pinfunction "Y_4") (pintype "passive"))
    )
    (net (code "48") (name "PGND") (class "Default")
      (node (ref "C18") (pin "1") (pinfunction "1_1") (pintype "passive"))
      (node (ref "C19") (pin "1") (pinfunction "1_1") (pintype "passive"))
      (node (ref "C20") (pin "1") (pinfunction "1_1") (pintype "passive"))
      (node (ref "C21") (pin "1") (pinfunction "1_1") (pintype "passive"))
      (node (ref "C24") (pin "1") (pinfunction "1_1") (pintype "passive"))
      (node (ref "C25") (pin "1") (pinfunction "1_1") (pintype "passive"))
      (node (ref "C26") (pin "1") (pinfunction "1_1") (pintype "passive"))
      (node (ref "C27") (pin "1") (pinfunction "1_1") (pintype "passive"))
      (node (ref "C28") (pin "2") (pinfunction "2_2") (pintype "passive"))
      (node (ref "C29") (pin "2") (pinfunction "2_2") (pintype "passive"))
      (node (ref "C31") (pin "2") (pinfunction "2_2") (pintype "passive"))
      (node (ref "C32") (pin "2") (pinfunction "2_2") (pintype "passive"))
      (node (ref "D12") (pin "1") (pinfunction "A_1") (pintype "passive"))
      (node (ref "D13") (pin "1") (pinfunction "A_1") (pintype "passive"))
      (node (ref "D23") (pin "1") (pinfunction "A_1") (pintype "passive"))
      (node (ref "D24") (pin "1") (pinfunction "A_1") (pintype "passive"))
      (node (ref "DZ3") (pin "1") (pinfunction "A_1") (pintype "passive"))
      (node (ref "DZ4") (pin "1") (pinfunction "A_1") (pintype "passive"))
      (node (ref "DZ7") (pin "1") (pinfunction "A_1") (pintype "passive"))
      (node (ref "DZ8") (pin "1") (pinfunction "A_1") (pintype "passive"))
      (node (ref "IC1") (pin "2") (pinfunction "GND_2") (pintype "passive"))
      (node (ref "Q10") (pin "1") (pinfunction "S_1") (pintype "passive"))
      (node (ref "Q10") (pin "2") (pinfunction "S_2") (pintype "passive"))
      (node (ref "Q10") (pin "3") (pinfunction "S_3") (pintype "passive"))
      (node (ref "Q5") (pin "1") (pinfunction "S_1") (pintype "passive"))
      (node (ref "Q5") (pin "2") (pinfunction "S_2") (pintype "passive"))
      (node (ref "Q5") (pin "3") (pinfunction "S_3") (pintype "passive"))
      (node (ref "Q6") (pin "1") (pinfunction "S_1") (pintype "passive"))
      (node (ref "Q6") (pin "2") (pinfunction "S_2") (pintype "passive"))
      (node (ref "Q6") (pin "3") (pinfunction "S_3") (pintype "passive"))
      (node (ref "Q9") (pin "1") (pinfunction "S_1") (pintype "passive"))
      (node (ref "Q9") (pin "2") (pinfunction "S_2") (pintype "passive"))
      (node (ref "Q9") (pin "3") (pinfunction "S_3") (pintype "passive"))
      (node (ref "R21") (pin "1") (pinfunction "1_1") (pintype "passive"))
      (node (ref "R22") (pin "1") (pinfunction "1_1") (pintype "passive"))
      (node (ref "R35") (pin "1") (pinfunction "1_1") (pintype "passive"))
      (node (ref "R36") (pin "1") (pinfunction "1_1") (pintype "passive"))
      (node (ref "R44") (pin "2") (pinfunction "2_2") (pintype "passive"))
      (node (ref "U2") (pin "4") (pinfunction "GND_4") (pintype "passive"))
      (node (ref "U3") (pin "4") (pinfunction "GND_4") (pintype "passive"))
      (node (ref "U4") (pin "4") (pinfunction "GND_4") (pintype "passive"))
      (node (ref "U5") (pin "4") (pinfunction "GND_4") (pintype "passive"))
    )
    (net (code "49") (name "PWM1") (class "Default")
      (node (ref "U2") (pin "2") (pinfunction "IN_2") (pintype "passive"))
    )
    (net (code "50") (name "PWM2") (class "Default")
      (node (ref "U3") (pin "2") (pinfunction "IN_2") (pintype "passive"))
    )
    (net (code "51") (name "PWM3") (class "Default")
      (node (ref "U4") (pin "2") (pinfunction "IN_2") (pintype "passive"))
    )
    (net (code "52") (name "PWM4") (class "Default")
      (node (ref "U5") (pin "2") (pinfunction "IN_2") (pintype "passive"))
    )
    (net (code "53") (name "SD1") (class "Default")
      (node (ref "R46") (pin "2") (pinfunction "2_2") (pintype "passive"))
      (node (ref "R47") (pin "1") (pinfunction "1_1") (pintype "passive"))
      (node (ref "U2") (pin "3") (pinfunction "SD#_3") (pintype "passive"))
      (node (ref "U3") (pin "3") (pinfunction "SD#_3") (pintype "passive"))
      (node (ref "U4") (pin "3") (pinfunction "SD#_3") (pintype "passive"))
      (node (ref "U5") (pin "3") (pinfunction "SD#_3") (pintype "passive"))
    )
    (net (code "54") (name "VOUT") (class "Default")
      (node (ref "C31") (pin "1") (pinfunction "1_1") (pintype "passive"))
      (node (ref "D16") (pin "2") (pinfunction "K_2") (pintype "passive"))
      (node (ref "D17") (pin "2") (pinfunction "K_2") (pintype "passive"))
      (node (ref "D5") (pin "2") (pinfunction "K_2") (pintype "passive"))
      (node (ref "D6") (pin "2") (pinfunction "K_2") (pintype "passive"))
      (node (ref "L3") (pin "1") (pinfunction "1_1") (pintype "passive"))
      (node (ref "Q3") (pin "5") (pinfunction "D_5") (pintype "passive"))
      (node (ref "Q3") (pin "6") (pinfunction "D_6") (pintype "passive"))
      (node (ref "Q3") (pin "7") (pinfunction "D_7") (pintype "passive"))
      (node (ref "Q3") (pin "8") (pinfunction "D_8") (pintype "passive"))
      (node (ref "Q3") (pin "9") (pinfunction "D_9") (pintype "passive"))
      (node (ref "Q4") (pin "5") (pinfunction "D_5") (pintype "passive"))
      (node (ref "Q4") (pin "6") (pinfunction "D_6") (pintype "passive"))
      (node (ref "Q4") (pin "7") (pinfunction "D_7") (pintype "passive"))
      (node (ref "Q4") (pin "8") (pinfunction "D_8") (pintype "passive"))
      (node (ref "Q4") (pin "9") (pinfunction "D_9") (pintype "passive"))
      (node (ref "Q7") (pin "5") (pinfunction "D_5") (pintype "passive"))
      (node (ref "Q7") (pin "6") (pinfunction "D_6") (pintype "passive"))
      (node (ref "Q7") (pin "7") (pinfunction "D_7") (pintype "passive"))
      (node (ref "Q7") (pin "8") (pinfunction "D_8") (pintype "passive"))
      (node (ref "Q7") (pin "9") (pinfunction "D_9") (pintype "passive"))
      (node (ref "Q8") (pin "5") (pinfunction "D_5") (pintype "passive"))
      (node (ref "Q8") (pin "6") (pinfunction "D_6") (pintype "passive"))
      (node (ref "Q8") (pin "7") (pinfunction "D_7") (pintype "passive"))
      (node (ref "Q8") (pin "8") (pinfunction "D_8") (pintype "passive"))
      (node (ref "Q8") (pin "9") (pinfunction "D_9") (pintype "passive"))
    )
    (net (code "55") (name "unconnected-(IC1-NC-Pad6)") (class "Default")
      (node (ref "IC1") (pin "6") (pinfunction "NC_6") (pintype "passive"))
    )
  )
)
